# HA_DC_Motor_Controller_V1_1.net
KiCad netlist of a schematic drawn in EAGLE
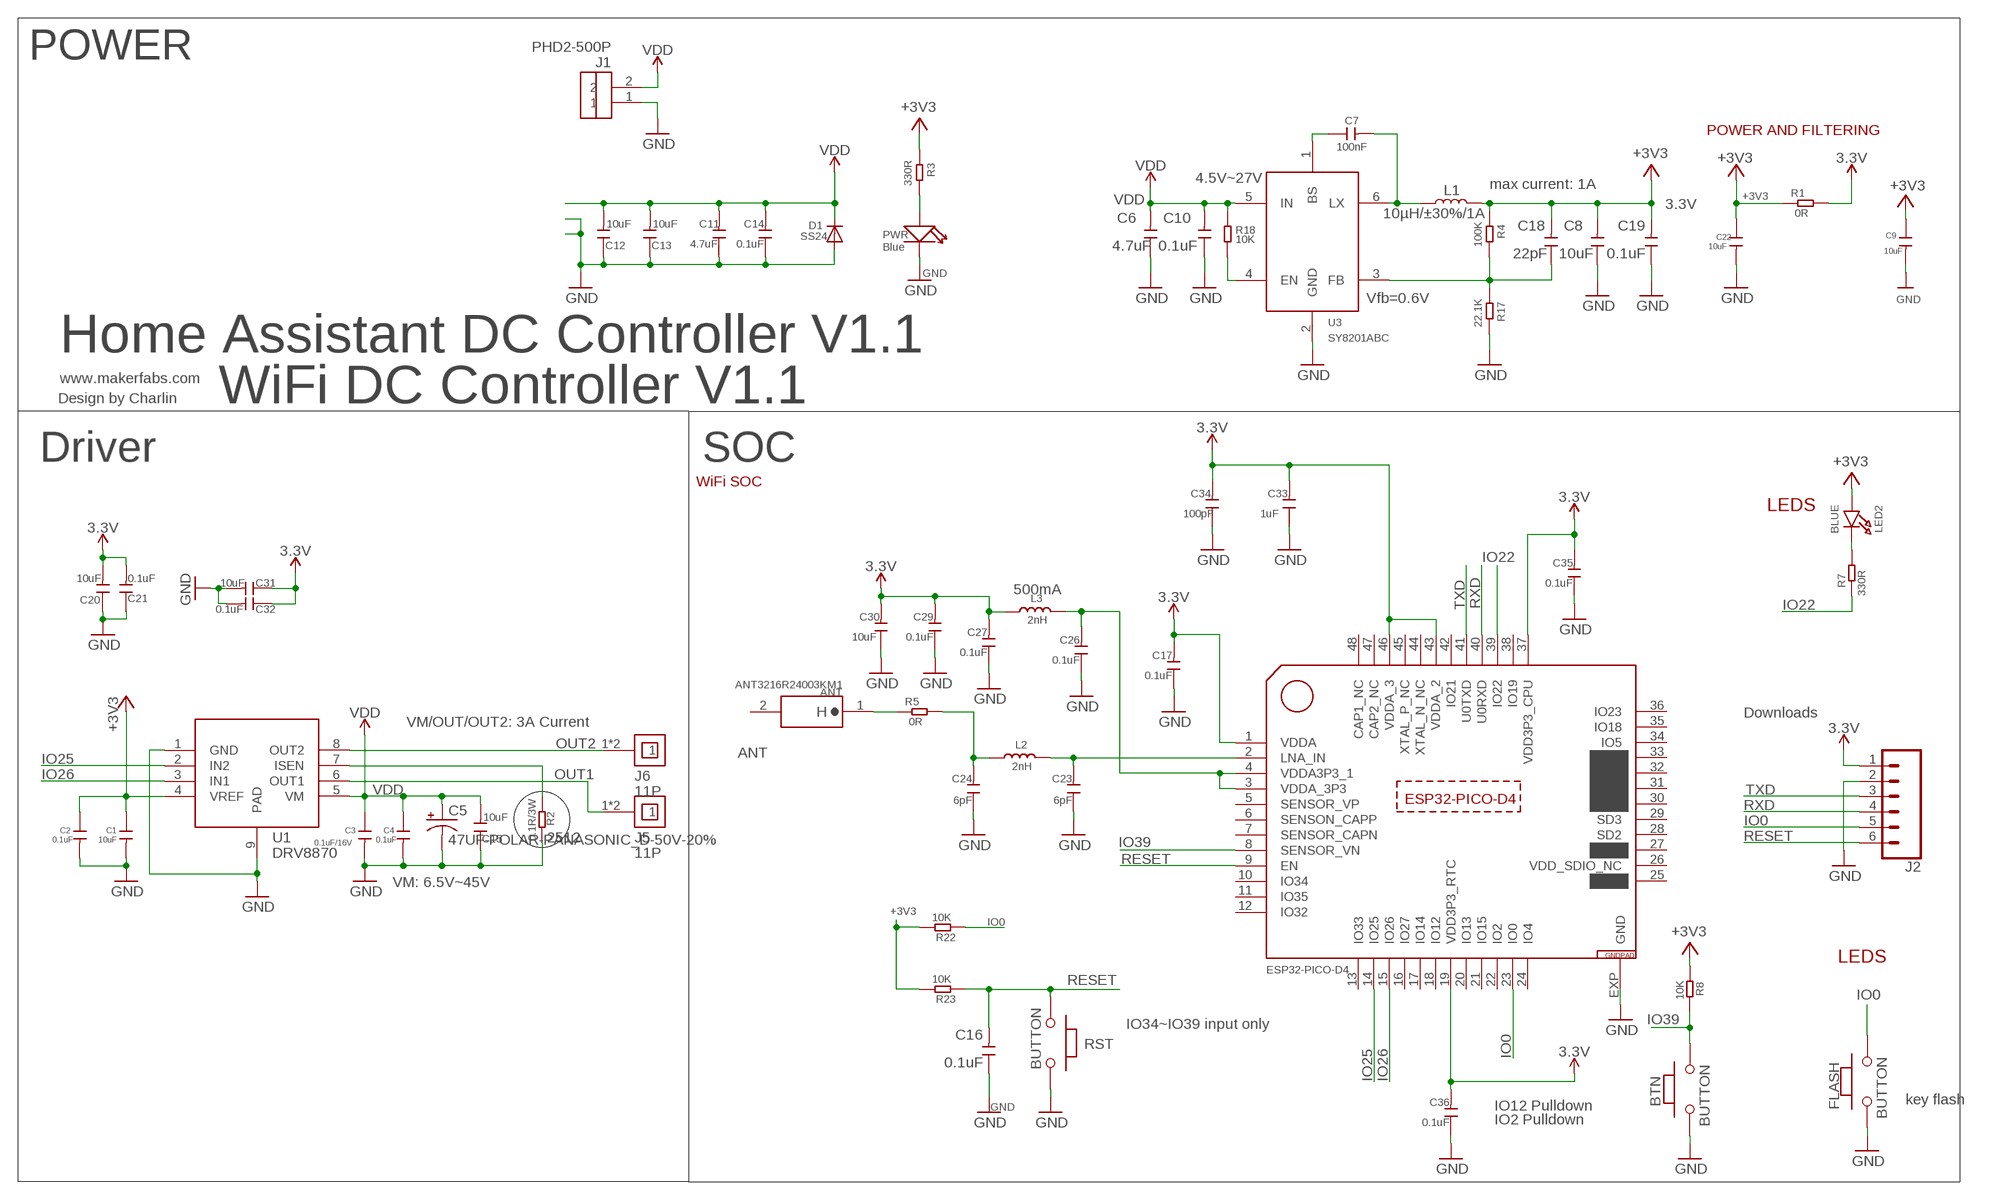
[diagram p0: schematic, sheet 1]

(export (version "E")
  (design (tool "Eeschema 10.0.6"))
  (components
    (comp (ref "ANT")
      (value "ANT3216R24003KM1")
      (footprint "eagle-import:ANT-1206")
      (libsource (lib "eagle-import") (part "ANT3216R24003KM1"))
    )
    (comp (ref "BTN")
      (value "BUTTON")
      (footprint "eagle-import:157SW")
      (libsource (lib "eagle-import") (part "PB157"))
    )
    (comp (ref "C1")
      (value "10uF")
      (footprint "eagle-import:0603")
      (libsource (lib "eagle-import") (part "C-0603"))
    )
    (comp (ref "C2")
      (value "0.1uF")
      (footprint "eagle-import:0603")
      (libsource (lib "eagle-import") (part "C-0603"))
    )
    (comp (ref "C3")
      (value "0.1uF/16V")
      (footprint "eagle-import:0603")
      (libsource (lib "eagle-import") (part "C-0603"))
    )
    (comp (ref "C4")
      (value "0.1uF")
      (footprint "eagle-import:0603")
      (libsource (lib "eagle-import") (part "C-0603"))
    )
    (comp (ref "C5")
      (value "47UF-POLAR-PANASONIC_D-50V-20%")
      (footprint "eagle-import:PANASONIC_D")
      (libsource (lib "eagle-import") (part "47UF-POLAR-PANASONIC_D-50V-20%"))
    )
    (comp (ref "C6")
      (value "4.7uF")
      (footprint "eagle-import:0603")
      (libsource (lib "eagle-import") (part "C-0603"))
    )
    (comp (ref "C7")
      (value "100nF")
      (footprint "eagle-import:0603")
      (libsource (lib "eagle-import") (part "C-0603"))
    )
    (comp (ref "C8")
      (value "10uF")
      (footprint "eagle-import:0603")
      (libsource (lib "eagle-import") (part "C-0603"))
    )
    (comp (ref "C9")
      (value "10uF")
      (footprint "eagle-import:0603")
      (libsource (lib "eagle-import") (part "C-0603"))
    )
    (comp (ref "C10")
      (value "0.1uF")
      (footprint "eagle-import:0603")
      (libsource (lib "eagle-import") (part "C-0603"))
    )
    (comp (ref "C11")
      (value "4.7uF")
      (footprint "eagle-import:0603")
      (libsource (lib "eagle-import") (part "C-0603"))
    )
    (comp (ref "C12")
      (value "10uF")
      (footprint "eagle-import:DISCRETE_C1206")
      (libsource (lib "eagle-import") (part "DISCRETE_C-1206"))
    )
    (comp (ref "C13")
      (value "10uF")
      (footprint "eagle-import:DISCRETE_C1206")
      (libsource (lib "eagle-import") (part "DISCRETE_C-1206"))
    )
    (comp (ref "C14")
      (value "0.1uF")
      (footprint "eagle-import:0603")
      (libsource (lib "eagle-import") (part "C-0603"))
    )
    (comp (ref "C15")
      (value "10uF")
      (footprint "eagle-import:DISCRETE_C1206")
      (libsource (lib "eagle-import") (part "DISCRETE_C-1206"))
    )
    (comp (ref "C16")
      (value "0.1uF")
      (footprint "eagle-import:0603")
      (libsource (lib "eagle-import") (part "C-0603"))
    )
    (comp (ref "C17")
      (value "0.1uF")
      (footprint "eagle-import:0603")
      (libsource (lib "eagle-import") (part "C-0603"))
    )
    (comp (ref "C18")
      (value "22pF")
      (footprint "eagle-import:0603")
      (libsource (lib "eagle-import") (part "C-0603"))
    )
    (comp (ref "C19")
      (value "0.1uF")
      (footprint "eagle-import:0603")
      (libsource (lib "eagle-import") (part "C-0603"))
    )
    (comp (ref "C20")
      (value "10uF")
      (footprint "eagle-import:DISCRETE_C0603")
      (libsource (lib "eagle-import") (part "DISCRETE_C-0603"))
    )
    (comp (ref "C21")
      (value "0.1uF")
      (footprint "eagle-import:DISCRETE_C0603")
      (libsource (lib "eagle-import") (part "DISCRETE_C-0603"))
    )
    (comp (ref "C22")
      (value "10uF")
      (footprint "eagle-import:0603")
      (libsource (lib "eagle-import") (part "C-0603"))
    )
    (comp (ref "C23")
      (value "6pF")
      (footprint "eagle-import:0603")
      (libsource (lib "eagle-import") (part "C-0603"))
    )
    (comp (ref "C24")
      (value "6pF")
      (footprint "eagle-import:0603")
      (libsource (lib "eagle-import") (part "C-0603"))
    )
    (comp (ref "C26")
      (value "0.1uF")
      (footprint "eagle-import:0603")
      (libsource (lib "eagle-import") (part "C-0603"))
    )
    (comp (ref "C27")
      (value "0.1uF")
      (footprint "eagle-import:0603")
      (libsource (lib "eagle-import") (part "C-0603"))
    )
    (comp (ref "C29")
      (value "0.1uF")
      (footprint "eagle-import:0603")
      (libsource (lib "eagle-import") (part "C-0603"))
    )
    (comp (ref "C30")
      (value "10uF")
      (footprint "eagle-import:0603")
      (libsource (lib "eagle-import") (part "C-0603"))
    )
    (comp (ref "C31")
      (value "10uF")
      (footprint "eagle-import:DISCRETE_C0603")
      (libsource (lib "eagle-import") (part "DISCRETE_C-0603"))
    )
    (comp (ref "C32")
      (value "0.1uF")
      (footprint "eagle-import:DISCRETE_C0603")
      (libsource (lib "eagle-import") (part "DISCRETE_C-0603"))
    )
    (comp (ref "C33")
      (value "1uF")
      (footprint "eagle-import:0603")
      (libsource (lib "eagle-import") (part "C-0603"))
    )
    (comp (ref "C34")
      (value "100pF")
      (footprint "eagle-import:0603")
      (libsource (lib "eagle-import") (part "C-0603"))
    )
    (comp (ref "C35")
      (value "0.1uF")
      (footprint "eagle-import:0603")
      (libsource (lib "eagle-import") (part "C-0603"))
    )
    (comp (ref "C36")
      (value "0.1uF")
      (footprint "eagle-import:0603")
      (libsource (lib "eagle-import") (part "C-0603"))
    )
    (comp (ref "D1")
      (value "SS24")
      (footprint "eagle-import:SMADIODE")
      (libsource (lib "eagle-import") (part "DIODESMA"))
    )
    (comp (ref "FLASH")
      (value "BUTTON")
      (footprint "eagle-import:157SW")
      (libsource (lib "eagle-import") (part "PB157"))
    )
    (comp (ref "J1")
      (value "PHD2-500P")
      (footprint "eagle-import:OPL_EAGLE_LIBRARY_2P-5.0")
      (libsource (lib "eagle-import") (part "PHD2-500P"))
    )
    (comp (ref "J2")
      (value "CONN_06SILK_FEMALE_PTH")
      (footprint "eagle-import:1X06")
      (libsource (lib "eagle-import") (part "CONN_06SILK_FEMALE_PTH"))
    )
    (comp (ref "J5")
      (value "11P")
      (footprint "eagle-import:1_1P-4_1MM")
      (libsource (lib "eagle-import") (part "11P"))
    )
    (comp (ref "J6")
      (value "11P")
      (footprint "eagle-import:1_1P-4_1MM")
      (libsource (lib "eagle-import") (part "11P"))
    )
    (comp (ref "L1")
      (value "10µH/±30%/1A")
      (footprint "eagle-import:CR54")
      (libsource (lib "eagle-import") (part "INDUCTOR-CR54-47UH"))
    )
    (comp (ref "L2")
      (value "2nH")
      (footprint "eagle-import:DISCRETE_L0603")
      (libsource (lib "eagle-import") (part "DISCRETE_L0603"))
    )
    (comp (ref "L3")
      (value "2nH")
      (footprint "eagle-import:DISCRETE_L0603")
      (libsource (lib "eagle-import") (part "DISCRETE_L0603"))
    )
    (comp (ref "LED2")
      (value "BLUE")
      (footprint "eagle-import:CHIPLED_0805_NOOUTLINE")
      (libsource (lib "eagle-import") (part "LED0805_NOOUTLINE"))
    )
    (comp (ref "PWR")
      (value "Blue")
      (footprint "eagle-import:LED-0603")
      (libsource (lib "eagle-import") (part "LED'0603'"))
    )
    (comp (ref "R1")
      (value "0R")
      (footprint "eagle-import:R0603")
      (libsource (lib "eagle-import") (part "R-0603"))
    )
    (comp (ref "R2")
      (value "0.1R/3W")
      (footprint "eagle-import:DISCRETE_R2512")
      (libsource (lib "eagle-import") (part "DISCRETE_R-2512"))
    )
    (comp (ref "R3")
      (value "330R")
      (footprint "eagle-import:R0603")
      (libsource (lib "eagle-import") (part "R-0603"))
    )
    (comp (ref "R4")
      (value "100K")
      (footprint "eagle-import:R0603")
      (libsource (lib "eagle-import") (part "R-0603"))
    )
    (comp (ref "R5")
      (value "0R")
      (footprint "eagle-import:R0603")
      (libsource (lib "eagle-import") (part "R-0603"))
    )
    (comp (ref "R7")
      (value "330R")
      (footprint "eagle-import:R0603")
      (libsource (lib "eagle-import") (part "R-0603"))
    )
    (comp (ref "R8")
      (value "10K")
      (footprint "eagle-import:R0603")
      (libsource (lib "eagle-import") (part "R-0603"))
    )
    (comp (ref "R17")
      (value "22.1K")
      (footprint "eagle-import:R0603")
      (libsource (lib "eagle-import") (part "R-0603"))
    )
    (comp (ref "R18")
      (value "10K")
      (footprint "eagle-import:R0603")
      (libsource (lib "eagle-import") (part "R-0603"))
    )
    (comp (ref "R22")
      (value "10K")
      (footprint "eagle-import:R0603")
      (libsource (lib "eagle-import") (part "R-0603"))
    )
    (comp (ref "R23")
      (value "10K")
      (footprint "eagle-import:R0603")
      (libsource (lib "eagle-import") (part "R-0603"))
    )
    (comp (ref "RST")
      (value "BUTTON")
      (footprint "eagle-import:157SW")
      (libsource (lib "eagle-import") (part "PB157"))
    )
    (comp (ref "U$2")
      (value "ESP32-PICO-D4")
      (footprint "eagle-import:QFN48")
      (libsource (lib "eagle-import") (part "ESP32-PICO-D4"))
    )
    (comp (ref "U1")
      (value "DRV8870")
      (footprint "eagle-import:SOP-8-EP")
      (libsource (lib "eagle-import") (part "DRV8870"))
    )
    (comp (ref "U3")
      (value "SY8201ABC")
      (footprint "eagle-import:SOT-23-6")
      (libsource (lib "eagle-import") (part "SY8201ABC"))
    )
  )
  (nets
    (net (code "1") (name "+3V3") (class "Default")
      (node (ref "C1") (pin "1") (pinfunction "1_1") (pintype "passive"))
      (node (ref "C18") (pin "2") (pinfunction "2_2") (pintype "passive"))
      (node (ref "C19") (pin "2") (pinfunction "2_2") (pintype "passive"))
      (node (ref "C2") (pin "1") (pinfunction "1_1") (pintype "passive"))
      (node (ref "C22") (pin "1") (pinfunction "1_1") (pintype "passive"))
      (node (ref "C8") (pin "2") (pinfunction "2_2") (pintype "passive"))
      (node (ref "C9") (pin "1") (pinfunction "1_1") (pintype "passive"))
      (node (ref "L1") (pin "P$2") (pinfunction "2_P$2") (pintype "passive"))
      (node (ref "LED2") (pin "A") (pinfunction "A_A") (pintype "passive"))
      (node (ref "R1") (pin "1") (pinfunction "1_1") (pintype "passive"))
      (node (ref "R22") (pin "2") (pinfunction "2_2") (pintype "passive"))
      (node (ref "R23") (pin "2") (pinfunction "2_2") (pintype "passive"))
      (node (ref "R3") (pin "1") (pinfunction "1_1") (pintype "passive"))
      (node (ref "R4") (pin "1") (pinfunction "1_1") (pintype "passive"))
      (node (ref "R8") (pin "1") (pinfunction "1_1") (pintype "passive"))
      (node (ref "U1") (pin "4") (pinfunction "VREF_4") (pintype "bidirectional"))
    )
    (net (code "2") (name "/IO0") (class "Default")
      (node (ref "FLASH") (pin "2") (pinfunction "2_2") (pintype "passive"))
      (node (ref "J2") (pin "5") (pinfunction "5_5") (pintype "passive"))
      (node (ref "R22") (pin "1") (pinfunction "1_1") (pintype "passive"))
      (node (ref "U$2") (pin "23") (pinfunction "IO0_23") (pintype "bidirectional"))
    )
    (net (code "3") (name "/IO22") (class "Default")
      (node (ref "R7") (pin "1") (pinfunction "1_1") (pintype "passive"))
      (node (ref "U$2") (pin "39") (pinfunction "IO22_39") (pintype "bidirectional"))
    )
    (net (code "4") (name "/IO25") (class "Default")
      (node (ref "U$2") (pin "14") (pinfunction "IO25_14") (pintype "bidirectional"))
      (node (ref "U1") (pin "2") (pinfunction "IN2_2") (pintype "bidirectional"))
    )
    (net (code "5") (name "/IO26") (class "Default")
      (node (ref "U$2") (pin "15") (pinfunction "IO26_15") (pintype "bidirectional"))
      (node (ref "U1") (pin "3") (pinfunction "IN1_3") (pintype "bidirectional"))
    )
    (net (code "6") (name "/IO39") (class "Default")
      (node (ref "BTN") (pin "2") (pinfunction "2_2") (pintype "passive"))
      (node (ref "R8") (pin "2") (pinfunction "2_2") (pintype "passive"))
      (node (ref "U$2") (pin "8") (pinfunction "SENSOR_VN_8") (pintype "input"))
    )
    (net (code "7") (name "/OUT1") (class "Default")
      (node (ref "J5") (pin "1") (pinfunction "1_1") (pintype "bidirectional"))
      (node (ref "J5") (pin "1@1") (pinfunction "1_1@1") (pintype "bidirectional"))
      (node (ref "U1") (pin "6") (pinfunction "OUT1_6") (pintype "bidirectional"))
    )
    (net (code "8") (name "/OUT2") (class "Default")
      (node (ref "J6") (pin "1") (pinfunction "1_1") (pintype "bidirectional"))
      (node (ref "J6") (pin "1@1") (pinfunction "1_1@1") (pintype "bidirectional"))
      (node (ref "U1") (pin "8") (pinfunction "OUT2_8") (pintype "bidirectional"))
    )
    (net (code "9") (name "/RESET") (class "Default")
      (node (ref "C16") (pin "2") (pinfunction "2_2") (pintype "passive"))
      (node (ref "J2") (pin "6") (pinfunction "6_6") (pintype "passive"))
      (node (ref "R23") (pin "1") (pinfunction "1_1") (pintype "passive"))
      (node (ref "RST") (pin "2") (pinfunction "2_2") (pintype "passive"))
      (node (ref "U$2") (pin "9") (pinfunction "EN_9") (pintype "input"))
    )
    (net (code "10") (name "/RXD") (class "Default")
      (node (ref "J2") (pin "4") (pinfunction "4_4") (pintype "passive"))
      (node (ref "U$2") (pin "40") (pinfunction "U0RXD_40") (pintype "bidirectional"))
    )
    (net (code "11") (name "/TXD") (class "Default")
      (node (ref "J2") (pin "3") (pinfunction "3_3") (pintype "passive"))
      (node (ref "U$2") (pin "41") (pinfunction "U0TXD_41") (pintype "bidirectional"))
    )
    (net (code "12") (name "/VDD_SDIO_NC") (class "Default")
      (node (ref "U$2") (pin "26") (pinfunction "VDD_SDIO_NC_26") (pintype "power_in"))
    )
    (net (code "13") (name "3.3V") (class "Default")
      (node (ref "C17") (pin "2") (pinfunction "2_2") (pintype "passive"))
      (node (ref "C20") (pin "2") (pinfunction "2_2") (pintype "passive"))
      (node (ref "C21") (pin "2") (pinfunction "2_2") (pintype "passive"))
      (node (ref "C27") (pin "2") (pinfunction "2_2") (pintype "passive"))
      (node (ref "C29") (pin "2") (pinfunction "2_2") (pintype "passive"))
      (node (ref "C30") (pin "2") (pinfunction "2_2") (pintype "passive"))
      (node (ref "C31") (pin "1") (pinfunction "1_1") (pintype "passive"))
      (node (ref "C32") (pin "1") (pinfunction "1_1") (pintype "passive"))
      (node (ref "C33") (pin "2") (pinfunction "2_2") (pintype "passive"))
      (node (ref "C34") (pin "2") (pinfunction "2_2") (pintype "passive"))
      (node (ref "C35") (pin "2") (pinfunction "2_2") (pintype "passive"))
      (node (ref "C36") (pin "2") (pinfunction "2_2") (pintype "passive"))
      (node (ref "J2") (pin "1") (pinfunction "1_1") (pintype "passive"))
      (node (ref "L3") (pin "1") (pinfunction "1_1") (pintype "passive"))
      (node (ref "R1") (pin "2") (pinfunction "2_2") (pintype "passive"))
      (node (ref "U$2") (pin "1") (pinfunction "VDDA_1") (pintype "power_in"))
      (node (ref "U$2") (pin "19") (pinfunction "VDD3P3_RTC_19") (pintype "power_in"))
      (node (ref "U$2") (pin "37") (pinfunction "VDD3P3_CPU_37") (pintype "power_in"))
      (node (ref "U$2") (pin "43") (pinfunction "VDDA_2_43") (pintype "power_in"))
      (node (ref "U$2") (pin "46") (pinfunction "VDDA_3_46") (pintype "power_in"))
    )
    (net (code "14") (name "GND") (class "Default")
      (node (ref "BTN") (pin "1") (pinfunction "1_1") (pintype "passive"))
      (node (ref "C1") (pin "2") (pinfunction "2_2") (pintype "passive"))
      (node (ref "C10") (pin "1") (pinfunction "1_1") (pintype "passive"))
      (node (ref "C11") (pin "1") (pinfunction "1_1") (pintype "passive"))
      (node (ref "C12") (pin "1") (pinfunction "1_1") (pintype "passive"))
      (node (ref "C13") (pin "1") (pinfunction "1_1") (pintype "passive"))
      (node (ref "C14") (pin "1") (pinfunction "1_1") (pintype "passive"))
      (node (ref "C15") (pin "1") (pinfunction "1_1") (pintype "passive"))
      (node (ref "C16") (pin "1") (pinfunction "1_1") (pintype "passive"))
      (node (ref "C17") (pin "1") (pinfunction "1_1") (pintype "passive"))
      (node (ref "C19") (pin "1") (pinfunction "1_1") (pintype "passive"))
      (node (ref "C2") (pin "2") (pinfunction "2_2") (pintype "passive"))
      (node (ref "C20") (pin "1") (pinfunction "1_1") (pintype "passive"))
      (node (ref "C21") (pin "1") (pinfunction "1_1") (pintype "passive"))
      (node (ref "C22") (pin "2") (pinfunction "2_2") (pintype "passive"))
      (node (ref "C23") (pin "1") (pinfunction "1_1") (pintype "passive"))
      (node (ref "C24") (pin "1") (pinfunction "1_1") (pintype "passive"))
      (node (ref "C26") (pin "1") (pinfunction "1_1") (pintype "passive"))
      (node (ref "C27") (pin "1") (pinfunction "1_1") (pintype "passive"))
      (node (ref "C29") (pin "1") (pinfunction "1_1") (pintype "passive"))
      (node (ref "C3") (pin "2") (pinfunction "2_2") (pintype "passive"))
      (node (ref "C30") (pin "1") (pinfunction "1_1") (pintype "passive"))
      (node (ref "C31") (pin "2") (pinfunction "2_2") (pintype "passive"))
      (node (ref "C32") (pin "2") (pinfunction "2_2") (pintype "passive"))
      (node (ref "C33") (pin "1") (pinfunction "1_1") (pintype "passive"))
      (node (ref "C34") (pin "1") (pinfunction "1_1") (pintype "passive"))
      (node (ref "C35") (pin "1") (pinfunction "1_1") (pintype "passive"))
      (node (ref "C36") (pin "1") (pinfunction "1_1") (pintype "passive"))
      (node (ref "C4") (pin "2") (pinfunction "2_2") (pintype "passive"))
      (node (ref "C5") (pin "-") (pinfunction "-_-") (pintype "passive"))
      (node (ref "C6") (pin "1") (pinfunction "1_1") (pintype "passive"))
      (node (ref "C8") (pin "1") (pinfunction "1_1") (pintype "passive"))
      (node (ref "C9") (pin "2") (pinfunction "2_2") (pintype "passive"))
      (node (ref "D1") (pin "A") (pinfunction "A_A") (pintype "passive"))
      (node (ref "FLASH") (pin "1") (pinfunction "1_1") (pintype "passive"))
      (node (ref "J1") (pin "1") (pinfunction "1_1") (pintype "bidirectional"))
      (node (ref "J2") (pin "2") (pinfunction "2_2") (pintype "passive"))
      (node (ref "PWR") (pin "-") (pinfunction "-_-") (pintype "passive"))
      (node (ref "R17") (pin "2") (pinfunction "2_2") (pintype "passive"))
      (node (ref "R2") (pin "1") (pinfunction "1_1") (pintype "passive"))
      (node (ref "RST") (pin "1") (pinfunction "1_1") (pintype "passive"))
      (node (ref "U$2") (pin "EXP") (pinfunction "GND_EXP") (pintype "power_in"))
      (node (ref "U1") (pin "1") (pinfunction "GND_1") (pintype "bidirectional"))
      (node (ref "U1") (pin "9") (pinfunction "PAD_9") (pintype "bidirectional"))
      (node (ref "U3") (pin "2") (pinfunction "GND_2") (pintype "bidirectional"))
    )
    (net (code "15") (name "Net-(ANT-Pad1)") (class "Default")
      (node (ref "ANT") (pin "1") (pinfunction "1_1") (pintype "bidirectional"))
      (node (ref "R5") (pin "1") (pinfunction "1_1") (pintype "passive"))
    )
    (net (code "16") (name "Net-(C24-Pad2)") (class "Default")
      (node (ref "C24") (pin "2") (pinfunction "2_2") (pintype "passive"))
      (node (ref "L2") (pin "1") (pinfunction "1_1") (pintype "passive"))
      (node (ref "R5") (pin "2") (pinfunction "2_2") (pintype "passive"))
    )
    (net (code "17") (name "Net-(L1-1)") (class "Default")
      (node (ref "C7") (pin "2") (pinfunction "2_2") (pintype "passive"))
      (node (ref "L1") (pin "P$1") (pinfunction "1_P$1") (pintype "passive"))
      (node (ref "U3") (pin "6") (pinfunction "LX_6") (pintype "bidirectional"))
    )
    (net (code "18") (name "Net-(LED2-PadC)") (class "Default")
      (node (ref "LED2") (pin "C") (pinfunction "C_C") (pintype "passive"))
      (node (ref "R7") (pin "2") (pinfunction "2_2") (pintype "passive"))
    )
    (net (code "19") (name "Net-(PWR-Pad+)") (class "Default")
      (node (ref "PWR") (pin "+") (pinfunction "+_+") (pintype "passive"))
      (node (ref "R3") (pin "2") (pinfunction "2_2") (pintype "passive"))
    )
    (net (code "20") (name "Net-(U$2-LNA_IN)") (class "Default")
      (node (ref "C23") (pin "2") (pinfunction "2_2") (pintype "passive"))
      (node (ref "L2") (pin "2") (pinfunction "2_2") (pintype "passive"))
      (node (ref "U$2") (pin "2") (pinfunction "LNA_IN_2") (pintype "bidirectional"))
    )
    (net (code "21") (name "Net-(U$2-VDDA3P3_1)") (class "Default")
      (node (ref "C26") (pin "2") (pinfunction "2_2") (pintype "passive"))
      (node (ref "L3") (pin "2") (pinfunction "2_2") (pintype "passive"))
      (node (ref "U$2") (pin "3") (pinfunction "VDDA_3P3_3") (pintype "power_in"))
      (node (ref "U$2") (pin "4") (pinfunction "VDDA3P3_1_4") (pintype "power_in"))
    )
    (net (code "22") (name "Net-(U1-ISEN)") (class "Default")
      (node (ref "R2") (pin "2") (pinfunction "2_2") (pintype "passive"))
      (node (ref "U1") (pin "7") (pinfunction "ISEN_7") (pintype "bidirectional"))
    )
    (net (code "23") (name "Net-(U3-BS)") (class "Default")
      (node (ref "C7") (pin "1") (pinfunction "1_1") (pintype "passive"))
      (node (ref "U3") (pin "1") (pinfunction "BS_1") (pintype "bidirectional"))
    )
    (net (code "24") (name "Net-(U3-EN)") (class "Default")
      (node (ref "R18") (pin "2") (pinfunction "2_2") (pintype "passive"))
      (node (ref "U3") (pin "4") (pinfunction "EN_4") (pintype "bidirectional"))
    )
    (net (code "25") (name "Net-(U3-FB)") (class "Default")
      (node (ref "C18") (pin "1") (pinfunction "1_1") (pintype "passive"))
      (node (ref "R17") (pin "1") (pinfunction "1_1") (pintype "passive"))
      (node (ref "R4") (pin "2") (pinfunction "2_2") (pintype "passive"))
      (node (ref "U3") (pin "3") (pinfunction "FB_3") (pintype "bidirectional"))
    )
    (net (code "26") (name "VDD") (class "Default")
      (node (ref "C10") (pin "2") (pinfunction "2_2") (pintype "passive"))
      (node (ref "C11") (pin "2") (pinfunction "2_2") (pintype "passive"))
      (node (ref "C12") (pin "2") (pinfunction "2_2") (pintype "passive"))
      (node (ref "C13") (pin "2") (pinfunction "2_2") (pintype "passive"))
      (node (ref "C14") (pin "2") (pinfunction "2_2") (pintype "passive"))
      (node (ref "C15") (pin "2") (pinfunction "2_2") (pintype "passive"))
      (node (ref "C3") (pin "1") (pinfunction "1_1") (pintype "passive"))
      (node (ref "C4") (pin "1") (pinfunction "1_1") (pintype "passive"))
      (node (ref "C5") (pin "+") (pinfunction "+_+") (pintype "passive"))
      (node (ref "C6") (pin "2") (pinfunction "2_2") (pintype "passive"))
      (node (ref "D1") (pin "C") (pinfunction "C_C") (pintype "passive"))
      (node (ref "J1") (pin "2") (pinfunction "2_2") (pintype "bidirectional"))
      (node (ref "R18") (pin "1") (pinfunction "1_1") (pintype "passive"))
      (node (ref "U1") (pin "5") (pinfunction "VM_5") (pintype "bidirectional"))
      (node (ref "U3") (pin "5") (pinfunction "IN_5") (pintype "bidirectional"))
    )
    (net (code "27") (name "unconnected-(ANT-Pad2)") (class "Default")
      (node (ref "ANT") (pin "2") (pinfunction "2_2") (pintype "bidirectional"))
    )
    (net (code "28") (name "unconnected-(U$2-CAP1_NC-Pad48)") (class "Default")
      (node (ref "U$2") (pin "48") (pinfunction "CAP1_NC_48") (pintype "bidirectional"))
    )
    (net (code "29") (name "unconnected-(U$2-CAP2_NC-Pad47)") (class "Default")
      (node (ref "U$2") (pin "47") (pinfunction "CAP2_NC_47") (pintype "bidirectional"))
    )
    (net (code "30") (name "unconnected-(U$2-CLK-Pad31)") (class "Default")
      (node (ref "U$2") (pin "31") (pinfunction "CLK_31") (pintype "bidirectional"))
    )
    (net (code "31") (name "unconnected-(U$2-CMD-Pad30)") (class "Default")
      (node (ref "U$2") (pin "30") (pinfunction "CMD_30") (pintype "bidirectional"))
    )
    (net (code "32") (name "unconnected-(U$2-IO2-Pad22)") (class "Default")
      (node (ref "U$2") (pin "22") (pinfunction "IO2_22") (pintype "bidirectional"))
    )
    (net (code "33") (name "unconnected-(U$2-IO4-Pad24)") (class "Default")
      (node (ref "U$2") (pin "24") (pinfunction "IO4_24") (pintype "bidirectional"))
    )
    (net (code "34") (name "unconnected-(U$2-IO5-Pad34)") (class "Default")
      (node (ref "U$2") (pin "34") (pinfunction "IO5_34") (pintype "bidirectional"))
    )
    (net (code "35") (name "unconnected-(U$2-IO12-Pad18)") (class "Default")
      (node (ref "U$2") (pin "18") (pinfunction "IO12_18") (pintype "bidirectional"))
    )
    (net (code "36") (name "unconnected-(U$2-IO13-Pad20)") (class "Default")
      (node (ref "U$2") (pin "20") (pinfunction "IO13_20") (pintype "bidirectional"))
    )
    (net (code "37") (name "unconnected-(U$2-IO14-Pad17)") (class "Default")
      (node (ref "U$2") (pin "17") (pinfunction "IO14_17") (pintype "bidirectional"))
    )
    (net (code "38") (name "unconnected-(U$2-IO15-Pad21)") (class "Default")
      (node (ref "U$2") (pin "21") (pinfunction "IO15_21") (pintype "bidirectional"))
    )
    (net (code "39") (name "unconnected-(U$2-IO16-Pad25)") (class "Default")
      (node (ref "U$2") (pin "25") (pinfunction "IO16_25") (pintype "bidirectional"))
    )
    (net (code "40") (name "unconnected-(U$2-IO17-Pad27)") (class "Default")
      (node (ref "U$2") (pin "27") (pinfunction "IO17_27") (pintype "bidirectional"))
    )
    (net (code "41") (name "unconnected-(U$2-IO18-Pad35)") (class "Default")
      (node (ref "U$2") (pin "35") (pinfunction "IO18_35") (pintype "bidirectional"))
    )
    (net (code "42") (name "unconnected-(U$2-IO19-Pad38)") (class "Default")
      (node (ref "U$2") (pin "38") (pinfunction "IO19_38") (pintype "bidirectional"))
    )
    (net (code "43") (name "unconnected-(U$2-IO21-Pad42)") (class "Default")
      (node (ref "U$2") (pin "42") (pinfunction "IO21_42") (pintype "bidirectional"))
    )
    (net (code "44") (name "unconnected-(U$2-IO23-Pad36)") (class "Default")
      (node (ref "U$2") (pin "36") (pinfunction "IO23_36") (pintype "bidirectional"))
    )
    (net (code "45") (name "unconnected-(U$2-IO27-Pad16)") (class "Default")
      (node (ref "U$2") (pin "16") (pinfunction "IO27_16") (pintype "bidirectional"))
    )
    (net (code "46") (name "unconnected-(U$2-IO32-Pad12)") (class "Default")
      (node (ref "U$2") (pin "12") (pinfunction "IO32_12") (pintype "bidirectional"))
    )
    (net (code "47") (name "unconnected-(U$2-IO33-Pad13)") (class "Default")
      (node (ref "U$2") (pin "13") (pinfunction "IO33_13") (pintype "bidirectional"))
    )
    (net (code "48") (name "unconnected-(U$2-IO34-Pad10)") (class "Default")
      (node (ref "U$2") (pin "10") (pinfunction "IO34_10") (pintype "bidirectional"))
    )
    (net (code "49") (name "unconnected-(U$2-IO35-Pad11)") (class "Default")
      (node (ref "U$2") (pin "11") (pinfunction "IO35_11") (pintype "bidirectional"))
    )
    (net (code "50") (name "unconnected-(U$2-SD0-Pad32)") (class "Default")
      (node (ref "U$2") (pin "32") (pinfunction "SD0_32") (pintype "bidirectional"))
    )
    (net (code "51") (name "unconnected-(U$2-SD1-Pad33)") (class "Default")
      (node (ref "U$2") (pin "33") (pinfunction "SD1_33") (pintype "bidirectional"))
    )
    (net (code "52") (name "unconnected-(U$2-SD2-Pad28)") (class "Default")
      (node (ref "U$2") (pin "28") (pinfunction "SD2_28") (pintype "bidirectional"))
    )
    (net (code "53") (name "unconnected-(U$2-SD3-Pad29)") (class "Default")
      (node (ref "U$2") (pin "29") (pinfunction "SD3_29") (pintype "bidirectional"))
    )
    (net (code "54") (name "unconnected-(U$2-SENSON_CAPP-Pad6)") (class "Default")
      (node (ref "U$2") (pin "6") (pinfunction "SENSON_CAPP_6") (pintype "input"))
    )
    (net (code "55") (name "unconnected-(U$2-SENSOR_CAPN-Pad7)") (class "Default")
      (node (ref "U$2") (pin "7") (pinfunction "SENSOR_CAPN_7") (pintype "input"))
    )
    (net (code "56") (name "unconnected-(U$2-SENSOR_VP-Pad5)") (class "Default")
      (node (ref "U$2") (pin "5") (pinfunction "SENSOR_VP_5") (pintype "input"))
    )
    (net (code "57") (name "unconnected-(U$2-XTAL_N_NC-Pad44)") (class "Default")
      (node (ref "U$2") (pin "44") (pinfunction "XTAL_N_NC_44") (pintype "bidirectional"))
    )
    (net (code "58") (name "unconnected-(U$2-XTAL_P_NC-Pad45)") (class "Default")
      (node (ref "U$2") (pin "45") (pinfunction "XTAL_P_NC_45") (pintype "bidirectional"))
    )
  )
)
